# Sheet1.net
KiCad netlist of a schematic drawn in Altium Designer
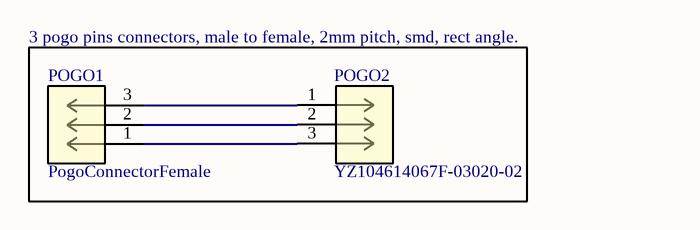
[diagram p0: Sheet1.SchDoc]

(export (version "E")
  (design (tool "Eeschema 10.0.6"))
  (components
    (comp (ref "POGO1")
      (value "PogoConnectorFemale")
      (footprint "PogoConnectorFemale")
      (libsource (lib "PogoPinConnPitch2mm3PinSMDHorizontalFemale") (part "PogoConnectorFemale"))
    )
    (comp (ref "POGO2")
      (value "YZ104614067F-03020-02")
      (footprint "YZ104614067F-03020-02")
      (description "Pogo pin connector, Pitch 2mm, SMD, Rectangular Angle, 3 Pins, Male")
      (libsource (lib "PogoPinConnPitch2mm3PinSMDHorizontal") (part "YZ104614067F-03020-02"))
    )
  )
  (nets
    (net (code "1") (name "Net-(POGO1-Pad1)") (class "Default")
      (node (ref "POGO1") (pin "1") (pinfunction "1_1") (pintype "passive"))
      (node (ref "POGO2") (pin "3") (pinfunction "3_3") (pintype "passive"))
    )
    (net (code "2") (name "Net-(POGO1-Pad2)") (class "Default")
      (node (ref "POGO1") (pin "2") (pinfunction "2_2") (pintype "passive"))
      (node (ref "POGO2") (pin "2") (pinfunction "2_2") (pintype "passive"))
    )
    (net (code "3") (name "Net-(POGO1-Pad3)") (class "Default")
      (node (ref "POGO1") (pin "3") (pinfunction "3_3") (pintype "passive"))
      (node (ref "POGO2") (pin "1") (pinfunction "1_1") (pintype "passive"))
    )
  )
)
